# dotclock.net
KiCad netlist of a schematic drawn in EAGLE
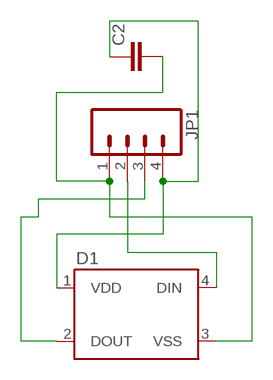
[diagram p0: schematic, sheet 1]

(export (version "E")
  (design (tool "Eeschema 10.0.6"))
  (components
    (comp (ref "C2")
      (value "CAP0805")
      (footprint "eagle-import:0805")
      (libsource (lib "eagle-import") (part "CAP0805"))
    )
    (comp (ref "D1")
      (value "WS2812B")
      (footprint "eagle-import:WS2812B")
      (libsource (lib "eagle-import") (part "WS2812B"))
    )
    (comp (ref "JP1")
      (value "M04NO_SILK_ALL_ROUND")
      (footprint "eagle-import:1X04_NO_SILK_ALL_ROUND")
      (libsource (lib "eagle-import") (part "M04NO_SILK_ALL_ROUND"))
    )
  )
  (nets
    (net (code "1") (name "Net-(D1-DIN)") (class "Default")
      (node (ref "D1") (pin "4") (pinfunction "DIN_4") (pintype "input"))
      (node (ref "JP1") (pin "2") (pinfunction "2_2") (pintype "passive"))
    )
    (net (code "2") (name "Net-(D1-DOUT)") (class "Default")
      (node (ref "D1") (pin "2") (pinfunction "DOUT_2") (pintype "output"))
      (node (ref "JP1") (pin "3") (pinfunction "3_3") (pintype "passive"))
    )
    (net (code "3") (name "Net-(D1-VDD)") (class "Default")
      (node (ref "C2") (pin "1") (pinfunction "1_1") (pintype "passive"))
      (node (ref "D1") (pin "1") (pinfunction "VDD_1") (pintype "power_in"))
      (node (ref "JP1") (pin "4") (pinfunction "4_4") (pintype "passive"))
    )
    (net (code "4") (name "Net-(D1-VSS)") (class "Default")
      (node (ref "C2") (pin "2") (pinfunction "2_2") (pintype "passive"))
      (node (ref "D1") (pin "3") (pinfunction "VSS_3") (pintype "power_in"))
      (node (ref "JP1") (pin "1") (pinfunction "1_1") (pintype "passive"))
    )
  )
)
